# projesonberna.net
KiCad netlist of a schematic drawn in EAGLE
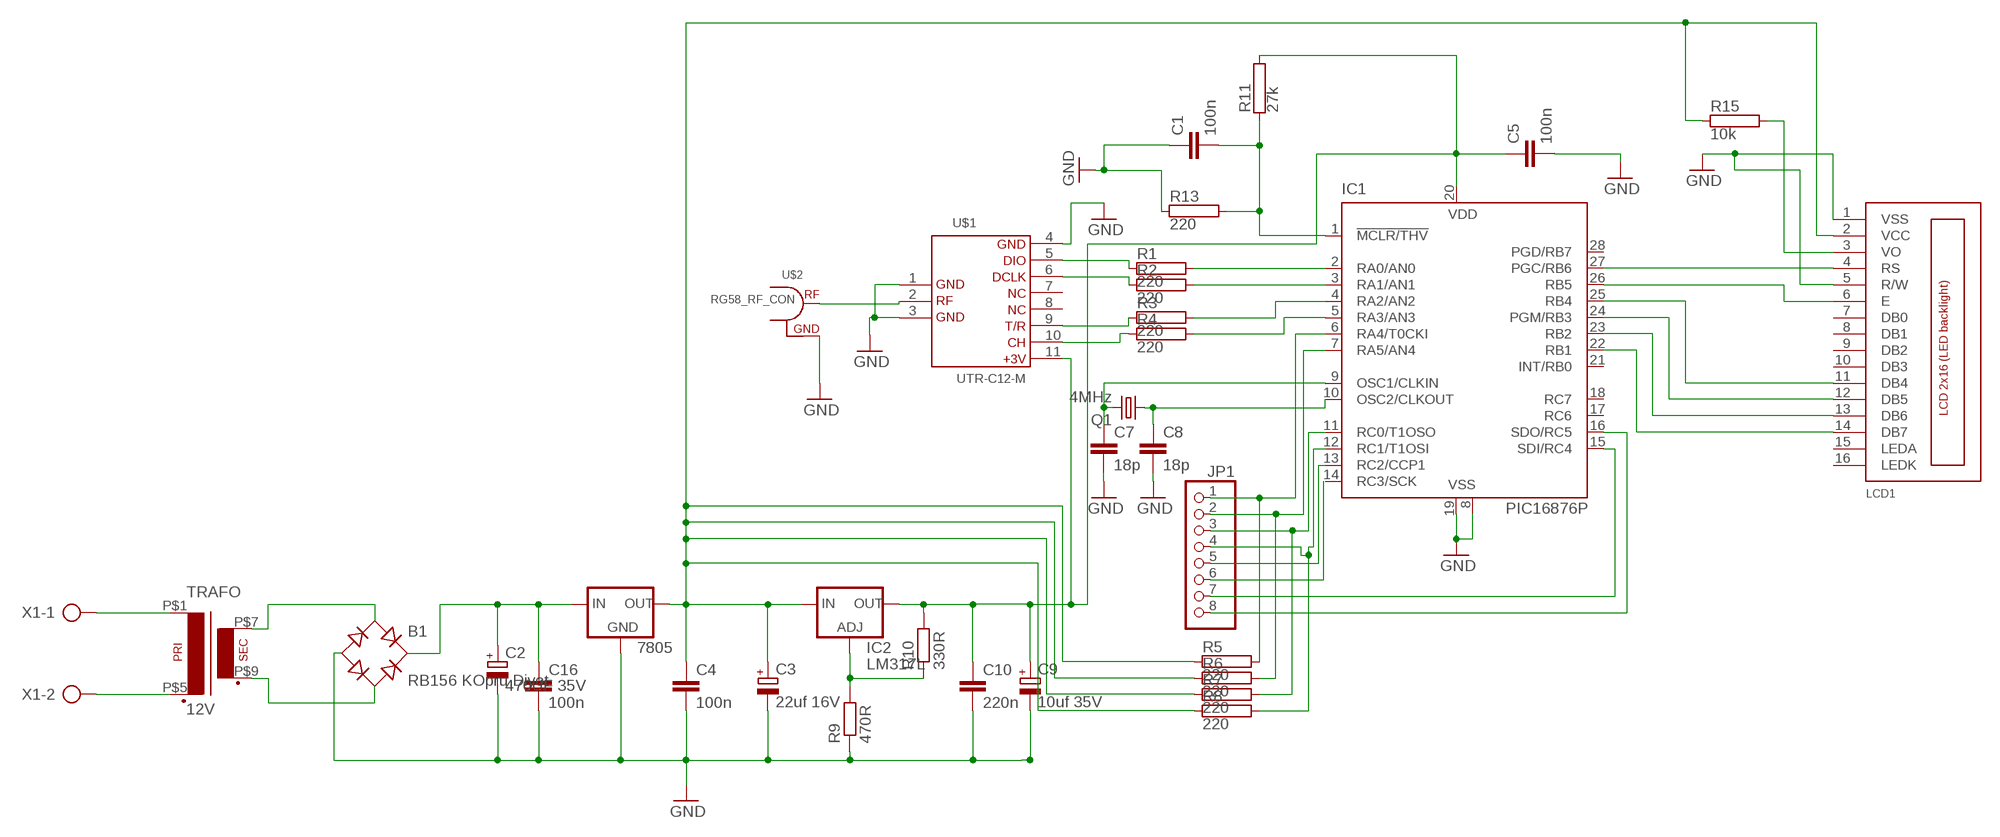
[diagram p0: schematic, sheet 1]

(export (version "E")
  (design (tool "Eeschema 10.0.6"))
  (components
    (comp (ref "7805")
      (value "78XXS")
      (footprint "eagle-import:78XXS")
      (libsource (lib "eagle-import") (part "78XXS"))
    )
    (comp (ref "B1")
      (value "RB156 KOpru Diyot")
      (footprint "eagle-import:RB1A")
      (libsource (lib "eagle-import") (part "RB1A"))
    )
    (comp (ref "C1")
      (value "100n")
      (footprint "eagle-import:C025-030X050")
      (libsource (lib "eagle-import") (part "C-EU025-030X050"))
    )
    (comp (ref "C2")
      (value "470UF 35V")
      (footprint "eagle-import:E3,5-10")
      (libsource (lib "eagle-import") (part "CPOL-EUE3.5-10"))
    )
    (comp (ref "C3")
      (value "22uf 16V")
      (footprint "eagle-import:E2,5-7")
      (libsource (lib "eagle-import") (part "CPOL-EUE2.5-7"))
    )
    (comp (ref "C4")
      (value "100n")
      (footprint "eagle-import:C050-025X075")
      (libsource (lib "eagle-import") (part "C-EU050-025X075"))
    )
    (comp (ref "C5")
      (value "100n")
      (footprint "eagle-import:C025-025X050")
      (libsource (lib "eagle-import") (part "C-EU025-025X050"))
    )
    (comp (ref "C7")
      (value "18p")
      (footprint "eagle-import:C025-025X050")
      (libsource (lib "eagle-import") (part "C-EU025-025X050"))
    )
    (comp (ref "C8")
      (value "18p")
      (footprint "eagle-import:C025-025X050")
      (libsource (lib "eagle-import") (part "C-EU025-025X050"))
    )
    (comp (ref "C9")
      (value "10uf 35V")
      (footprint "eagle-import:E2,5-7")
      (libsource (lib "eagle-import") (part "CPOL-EUE2.5-7"))
    )
    (comp (ref "C10")
      (value "220n")
      (footprint "eagle-import:C050-025X075")
      (libsource (lib "eagle-import") (part "C-EU050-025X075"))
    )
    (comp (ref "C16")
      (value "100n")
      (footprint "eagle-import:C050-025X075")
      (libsource (lib "eagle-import") (part "C-EU050-025X075"))
    )
    (comp (ref "IC1")
      (value "PIC16876P")
      (footprint "eagle-import:DIL28-3")
      (libsource (lib "eagle-import") (part "PIC16876P"))
    )
    (comp (ref "IC2")
      (value "LM317L")
      (footprint "eagle-import:317L")
      (libsource (lib "eagle-import") (part "LM317L"))
    )
    (comp (ref "JP1")
      (value "PINHD-1X8")
      (footprint "eagle-import:1X08")
      (libsource (lib "eagle-import") (part "PINHD-1X8"))
    )
    (comp (ref "LCD1")
      (value "LCD_2X16_SIL")
      (footprint "eagle-import:HY-1602F")
      (libsource (lib "eagle-import") (part "LCD_2X16_SIL"))
    )
    (comp (ref "Q1")
      (value "4MHz")
      (footprint "eagle-import:HC49_S")
      (libsource (lib "eagle-import") (part "CRYTALHC49S"))
    )
    (comp (ref "R1")
      (value "220")
      (footprint "eagle-import:AC04")
      (libsource (lib "eagle-import") (part "RAC04"))
    )
    (comp (ref "R2")
      (value "220")
      (footprint "eagle-import:AC04")
      (libsource (lib "eagle-import") (part "RAC04"))
    )
    (comp (ref "R3")
      (value "220")
      (footprint "eagle-import:AC04")
      (libsource (lib "eagle-import") (part "RAC04"))
    )
    (comp (ref "R4")
      (value "220")
      (footprint "eagle-import:AC04")
      (libsource (lib "eagle-import") (part "RAC04"))
    )
    (comp (ref "R5")
      (value "220")
      (footprint "eagle-import:AC04")
      (libsource (lib "eagle-import") (part "RAC04"))
    )
    (comp (ref "R6")
      (value "220")
      (footprint "eagle-import:AC04")
      (libsource (lib "eagle-import") (part "RAC04"))
    )
    (comp (ref "R7")
      (value "220")
      (footprint "eagle-import:AC04")
      (libsource (lib "eagle-import") (part "RAC04"))
    )
    (comp (ref "R8")
      (value "220")
      (footprint "eagle-import:AC04")
      (libsource (lib "eagle-import") (part "RAC04"))
    )
    (comp (ref "R9")
      (value "470R")
      (footprint "eagle-import:0207_10")
      (libsource (lib "eagle-import") (part "R-EU_0207/10"))
    )
    (comp (ref "R10")
      (value "330R")
      (footprint "eagle-import:0207_10")
      (libsource (lib "eagle-import") (part "R-EU_0207/10"))
    )
    (comp (ref "R11")
      (value "27k")
      (footprint "eagle-import:AC04")
      (libsource (lib "eagle-import") (part "RAC04"))
    )
    (comp (ref "R13")
      (value "220")
      (footprint "eagle-import:AC04")
      (libsource (lib "eagle-import") (part "RAC04"))
    )
    (comp (ref "R15")
      (value "10k")
      (footprint "eagle-import:AC04")
      (libsource (lib "eagle-import") (part "RAC04"))
    )
    (comp (ref "TRAFO")
      (value "12V")
      (footprint "eagle-import:E3031TRF")
      (libsource (lib "eagle-import") (part "TRAFO"))
    )
    (comp (ref "U$1")
      (value "UTR-C12-M")
      (footprint "eagle-import:UTR-C12-M")
      (libsource (lib "eagle-import") (part "UTR-C12-M"))
    )
    (comp (ref "U$2")
      (value "RG58_RF_CON")
      (footprint "eagle-import:RG58_RF_CON")
      (libsource (lib "eagle-import") (part "RG58_RF_CON"))
    )
    (comp (ref "X1")
      (value "AK300/3")
      (footprint "eagle-import:AK300_3")
      (libsource (lib "eagle-import") (part "AK300/3"))
    )
  )
  (nets
    (net (code "1") (name "GND") (class "Default")
      (node (ref "7805") (pin "GND") (pinfunction "GND_GND") (pintype "input"))
      (node (ref "B1") (pin "-") (pinfunction "-_-") (pintype "passive"))
      (node (ref "C1") (pin "1") (pinfunction "1_1") (pintype "passive"))
      (node (ref "C10") (pin "2") (pinfunction "2_2") (pintype "passive"))
      (node (ref "C16") (pin "2") (pinfunction "2_2") (pintype "passive"))
      (node (ref "C2") (pin "-") (pinfunction "-_-") (pintype "passive"))
      (node (ref "C3") (pin "-") (pinfunction "-_-") (pintype "passive"))
      (node (ref "C4") (pin "2") (pinfunction "2_2") (pintype "passive"))
      (node (ref "C5") (pin "2") (pinfunction "2_2") (pintype "passive"))
      (node (ref "C7") (pin "2") (pinfunction "2_2") (pintype "passive"))
      (node (ref "C8") (pin "2") (pinfunction "2_2") (pintype "passive"))
      (node (ref "C9") (pin "-") (pinfunction "-_-") (pintype "passive"))
      (node (ref "IC1") (pin "19") (pinfunction "VSS_19") (pintype "power_in"))
      (node (ref "IC1") (pin "8") (pinfunction "VSS_8") (pintype "power_in"))
      (node (ref "LCD1") (pin "1") (pinfunction "VSS_1") (pintype "power_in"))
      (node (ref "LCD1") (pin "5") (pinfunction "R/W_5") (pintype "input"))
      (node (ref "R13") (pin "1") (pinfunction "1_1") (pintype "passive"))
      (node (ref "R9") (pin "1") (pinfunction "1_1") (pintype "passive"))
      (node (ref "U$1") (pin "1") (pinfunction "1_1") (pintype "bidirectional"))
      (node (ref "U$1") (pin "3") (pinfunction "3_3") (pintype "bidirectional"))
      (node (ref "U$1") (pin "4") (pinfunction "4_4") (pintype "bidirectional"))
      (node (ref "U$2") (pin "GND") (pinfunction "GND_GND") (pintype "bidirectional"))
    )
    (net (code "2") (name "Net-(7805-PadIN)") (class "Default")
      (node (ref "7805") (pin "IN") (pinfunction "IN_IN") (pintype "input"))
      (node (ref "B1") (pin "+") (pinfunction "+_+") (pintype "passive"))
      (node (ref "C16") (pin "1") (pinfunction "1_1") (pintype "passive"))
      (node (ref "C2") (pin "+") (pinfunction "+_+") (pintype "passive"))
    )
    (net (code "3") (name "Net-(IC1-OSC1{slash}CLKIN)") (class "Default")
      (node (ref "C7") (pin "1") (pinfunction "1_1") (pintype "passive"))
      (node (ref "IC1") (pin "9") (pinfunction "OSC1/CLKIN_9") (pintype "input"))
      (node (ref "Q1") (pin "2") (pinfunction "2_2") (pintype "passive"))
    )
    (net (code "4") (name "Net-(IC1-OSC2{slash}CLKOUT)") (class "Default")
      (node (ref "C8") (pin "1") (pinfunction "1_1") (pintype "passive"))
      (node (ref "IC1") (pin "10") (pinfunction "OSC2/CLKOUT_10") (pintype "output"))
      (node (ref "Q1") (pin "1") (pinfunction "1_1") (pintype "passive"))
    )
    (net (code "5") (name "Net-(IC1-PGC{slash}RB6)") (class "Default")
      (node (ref "IC1") (pin "27") (pinfunction "PGC/RB6_27") (pintype "bidirectional"))
      (node (ref "LCD1") (pin "4") (pinfunction "RS_4") (pintype "input"))
    )
    (net (code "6") (name "Net-(IC1-PGM{slash}RB3)") (class "Default")
      (node (ref "IC1") (pin "24") (pinfunction "PGM/RB3_24") (pintype "bidirectional"))
      (node (ref "LCD1") (pin "12") (pinfunction "DB5_12") (pintype "bidirectional"))
    )
    (net (code "7") (name "Net-(IC1-RA0{slash}AN0)") (class "Default")
      (node (ref "IC1") (pin "2") (pinfunction "RA0/AN0_2") (pintype "bidirectional"))
      (node (ref "R1") (pin "2") (pinfunction "2_2") (pintype "passive"))
    )
    (net (code "8") (name "Net-(IC1-RA1{slash}AN1)") (class "Default")
      (node (ref "IC1") (pin "3") (pinfunction "RA1/AN1_3") (pintype "bidirectional"))
      (node (ref "R2") (pin "2") (pinfunction "2_2") (pintype "passive"))
    )
    (net (code "9") (name "Net-(IC1-RA2{slash}AN2)") (class "Default")
      (node (ref "IC1") (pin "4") (pinfunction "RA2/AN2_4") (pintype "bidirectional"))
      (node (ref "R3") (pin "2") (pinfunction "2_2") (pintype "passive"))
    )
    (net (code "10") (name "Net-(IC1-RA3{slash}AN3)") (class "Default")
      (node (ref "IC1") (pin "5") (pinfunction "RA3/AN3_5") (pintype "bidirectional"))
      (node (ref "R4") (pin "2") (pinfunction "2_2") (pintype "passive"))
    )
    (net (code "11") (name "Net-(IC1-RA4{slash}T0CKI)") (class "Default")
      (node (ref "IC1") (pin "6") (pinfunction "RA4/T0CKI_6") (pintype "bidirectional"))
      (node (ref "JP1") (pin "1") (pinfunction "1_1") (pintype "passive"))
      (node (ref "R5") (pin "2") (pinfunction "2_2") (pintype "passive"))
    )
    (net (code "12") (name "Net-(IC1-RA5{slash}AN4)") (class "Default")
      (node (ref "IC1") (pin "7") (pinfunction "RA5/AN4_7") (pintype "bidirectional"))
      (node (ref "JP1") (pin "2") (pinfunction "2_2") (pintype "passive"))
      (node (ref "R6") (pin "2") (pinfunction "2_2") (pintype "passive"))
    )
    (net (code "13") (name "Net-(IC1-RB1)") (class "Default")
      (node (ref "IC1") (pin "22") (pinfunction "RB1_22") (pintype "bidirectional"))
      (node (ref "LCD1") (pin "14") (pinfunction "DB7_14") (pintype "bidirectional"))
    )
    (net (code "14") (name "Net-(IC1-RB2)") (class "Default")
      (node (ref "IC1") (pin "23") (pinfunction "RB2_23") (pintype "bidirectional"))
      (node (ref "LCD1") (pin "13") (pinfunction "DB6_13") (pintype "bidirectional"))
    )
    (net (code "15") (name "Net-(IC1-RB4)") (class "Default")
      (node (ref "IC1") (pin "25") (pinfunction "RB4_25") (pintype "bidirectional"))
      (node (ref "LCD1") (pin "11") (pinfunction "DB4_11") (pintype "bidirectional"))
    )
    (net (code "16") (name "Net-(IC1-RB5)") (class "Default")
      (node (ref "IC1") (pin "26") (pinfunction "RB5_26") (pintype "bidirectional"))
      (node (ref "LCD1") (pin "6") (pinfunction "E_6") (pintype "input"))
    )
    (net (code "17") (name "Net-(IC1-RC0{slash}T1OSO)") (class "Default")
      (node (ref "IC1") (pin "11") (pinfunction "RC0/T1OSO_11") (pintype "bidirectional"))
      (node (ref "JP1") (pin "3") (pinfunction "3_3") (pintype "passive"))
      (node (ref "R7") (pin "2") (pinfunction "2_2") (pintype "passive"))
    )
    (net (code "18") (name "Net-(IC1-RC1{slash}T1OSI)") (class "Default")
      (node (ref "IC1") (pin "12") (pinfunction "RC1/T1OSI_12") (pintype "bidirectional"))
      (node (ref "JP1") (pin "4") (pinfunction "4_4") (pintype "passive"))
      (node (ref "R8") (pin "2") (pinfunction "2_2") (pintype "passive"))
    )
    (net (code "19") (name "Net-(IC1-RC2{slash}CCP1)") (class "Default")
      (node (ref "IC1") (pin "13") (pinfunction "RC2/CCP1_13") (pintype "bidirectional"))
      (node (ref "JP1") (pin "5") (pinfunction "5_5") (pintype "passive"))
    )
    (net (code "20") (name "Net-(IC1-SDI{slash}RC4)") (class "Default")
      (node (ref "IC1") (pin "15") (pinfunction "SDI/RC4_15") (pintype "bidirectional"))
      (node (ref "JP1") (pin "7") (pinfunction "7_7") (pintype "passive"))
    )
    (net (code "21") (name "Net-(IC1-SDO{slash}RC5)") (class "Default")
      (node (ref "IC1") (pin "16") (pinfunction "SDO/RC5_16") (pintype "bidirectional"))
      (node (ref "JP1") (pin "8") (pinfunction "8_8") (pintype "passive"))
    )
    (net (code "22") (name "Net-(IC1-VDD)") (class "Default")
      (node (ref "C10") (pin "1") (pinfunction "1_1") (pintype "passive"))
      (node (ref "C5") (pin "1") (pinfunction "1_1") (pintype "passive"))
      (node (ref "C9") (pin "+") (pinfunction "+_+") (pintype "passive"))
      (node (ref "IC1") (pin "20") (pinfunction "VDD_20") (pintype "power_in"))
      (node (ref "IC2") (pin "2") (pinfunction "OUT_2") (pintype "passive"))
      (node (ref "R10") (pin "2") (pinfunction "2_2") (pintype "passive"))
      (node (ref "R11") (pin "2") (pinfunction "2_2") (pintype "passive"))
      (node (ref "U$1") (pin "11") (pinfunction "11_11") (pintype "bidirectional"))
    )
    (net (code "23") (name "Net-(IC1-~{MCLR{slash}THV})") (class "Default")
      (node (ref "C1") (pin "2") (pinfunction "2_2") (pintype "passive"))
      (node (ref "IC1") (pin "1") (pinfunction "~{MCLR/THV}_1") (pintype "input"))
      (node (ref "R11") (pin "1") (pinfunction "1_1") (pintype "passive"))
      (node (ref "R13") (pin "2") (pinfunction "2_2") (pintype "passive"))
    )
    (net (code "24") (name "Net-(IC2-ADJ)") (class "Default")
      (node (ref "IC2") (pin "1") (pinfunction "ADJ_1") (pintype "input"))
      (node (ref "R10") (pin "1") (pinfunction "1_1") (pintype "passive"))
      (node (ref "R9") (pin "2") (pinfunction "2_2") (pintype "passive"))
    )
    (net (code "25") (name "Net-(IC2-IN)") (class "Default")
      (node (ref "7805") (pin "OUT") (pinfunction "OUT_OUT") (pintype "passive"))
      (node (ref "C3") (pin "+") (pinfunction "+_+") (pintype "passive"))
      (node (ref "C4") (pin "1") (pinfunction "1_1") (pintype "passive"))
      (node (ref "IC2") (pin "3") (pinfunction "IN_3") (pintype "input"))
      (node (ref "LCD1") (pin "2") (pinfunction "VCC_2") (pintype "power_in"))
      (node (ref "R15") (pin "1") (pinfunction "1_1") (pintype "passive"))
      (node (ref "R5") (pin "1") (pinfunction "1_1") (pintype "passive"))
      (node (ref "R6") (pin "1") (pinfunction "1_1") (pintype "passive"))
      (node (ref "R7") (pin "1") (pinfunction "1_1") (pintype "passive"))
      (node (ref "R8") (pin "1") (pinfunction "1_1") (pintype "passive"))
    )
    (net (code "26") (name "Net-(LCD1-VO)") (class "Default")
      (node (ref "LCD1") (pin "3") (pinfunction "VO_3") (pintype "input"))
      (node (ref "R15") (pin "2") (pinfunction "2_2") (pintype "passive"))
    )
    (net (code "27") (name "Net-(R1-Pad1)") (class "Default")
      (node (ref "R1") (pin "1") (pinfunction "1_1") (pintype "passive"))
      (node (ref "U$1") (pin "5") (pinfunction "5_5") (pintype "bidirectional"))
    )
    (net (code "28") (name "Net-(R2-Pad1)") (class "Default")
      (node (ref "R2") (pin "1") (pinfunction "1_1") (pintype "passive"))
      (node (ref "U$1") (pin "6") (pinfunction "6_6") (pintype "bidirectional"))
    )
    (net (code "29") (name "Net-(R3-Pad1)") (class "Default")
      (node (ref "R3") (pin "1") (pinfunction "1_1") (pintype "passive"))
      (node (ref "U$1") (pin "9") (pinfunction "9_9") (pintype "bidirectional"))
    )
    (net (code "30") (name "Net-(R4-Pad1)") (class "Default")
      (node (ref "R4") (pin "1") (pinfunction "1_1") (pintype "passive"))
      (node (ref "U$1") (pin "10") (pinfunction "10_10") (pintype "bidirectional"))
    )
    (net (code "31") (name "Net-(TRAFO-1)") (class "Default")
      (node (ref "TRAFO") (pin "P$1") (pinfunction "1_P$1") (pintype "passive"))
      (node (ref "X1") (pin "1") (pinfunction "KL_1") (pintype "passive"))
    )
    (net (code "32") (name "Net-(TRAFO-5)") (class "Default")
      (node (ref "TRAFO") (pin "P$5") (pinfunction "5_P$5") (pintype "passive"))
      (node (ref "X1") (pin "2") (pinfunction "KL_2") (pintype "passive"))
    )
    (net (code "33") (name "Net-(TRAFO-7)") (class "Default")
      (node (ref "B1") (pin "AC1") (pinfunction "AC1_AC1") (pintype "passive"))
      (node (ref "TRAFO") (pin "P$7") (pinfunction "7_P$7") (pintype "passive"))
    )
    (net (code "34") (name "Net-(TRAFO-9)") (class "Default")
      (node (ref "B1") (pin "AC2") (pinfunction "AC2_AC2") (pintype "passive"))
      (node (ref "TRAFO") (pin "P$9") (pinfunction "9_P$9") (pintype "passive"))
    )
    (net (code "35") (name "Net-(U$1-Pad2)") (class "Default")
      (node (ref "U$1") (pin "2") (pinfunction "2_2") (pintype "bidirectional"))
      (node (ref "U$2") (pin "RF") (pinfunction "RF_RF") (pintype "bidirectional"))
    )
    (net (code "36") (name "unconnected-(IC1-INT{slash}RB0-Pad21)") (class "Default")
      (node (ref "IC1") (pin "21") (pinfunction "INT/RB0_21") (pintype "bidirectional"))
    )
    (net (code "37") (name "unconnected-(IC1-PGD{slash}RB7-Pad28)") (class "Default")
      (node (ref "IC1") (pin "28") (pinfunction "PGD/RB7_28") (pintype "bidirectional"))
    )
    (net (code "38") (name "unconnected-(IC1-RC3{slash}SCK-Pad14)") (class "Default")
      (node (ref "IC1") (pin "14") (pinfunction "RC3/SCK_14") (pintype "bidirectional"))
    )
    (net (code "39") (name "unconnected-(IC1-RC6-Pad17)") (class "Default")
      (node (ref "IC1") (pin "17") (pinfunction "RC6_17") (pintype "bidirectional"))
    )
    (net (code "40") (name "unconnected-(IC1-RC7-Pad18)") (class "Default")
      (node (ref "IC1") (pin "18") (pinfunction "RC7_18") (pintype "bidirectional"))
    )
    (net (code "41") (name "unconnected-(JP1-Pad6)") (class "Default")
      (node (ref "JP1") (pin "6") (pinfunction "6_6") (pintype "passive"))
    )
    (net (code "42") (name "unconnected-(LCD1-DB0-Pad7)") (class "Default")
      (node (ref "LCD1") (pin "7") (pinfunction "DB0_7") (pintype "bidirectional"))
    )
    (net (code "43") (name "unconnected-(LCD1-DB1-Pad8)") (class "Default")
      (node (ref "LCD1") (pin "8") (pinfunction "DB1_8") (pintype "bidirectional"))
    )
    (net (code "44") (name "unconnected-(LCD1-DB2-Pad9)") (class "Default")
      (node (ref "LCD1") (pin "9") (pinfunction "DB2_9") (pintype "bidirectional"))
    )
    (net (code "45") (name "unconnected-(LCD1-DB3-Pad10)") (class "Default")
      (node (ref "LCD1") (pin "10") (pinfunction "DB3_10") (pintype "bidirectional"))
    )
    (net (code "46") (name "unconnected-(LCD1-LEDA-Pad15)") (class "Default")
      (node (ref "LCD1") (pin "15") (pinfunction "LEDA_15") (pintype "passive"))
    )
    (net (code "47") (name "unconnected-(LCD1-LEDK-Pad16)") (class "Default")
      (node (ref "LCD1") (pin "16") (pinfunction "LEDK_16") (pintype "passive"))
    )
    (net (code "48") (name "unconnected-(U$1-Pad7)") (class "Default")
      (node (ref "U$1") (pin "7") (pinfunction "7_7") (pintype "bidirectional"))
    )
    (net (code "49") (name "unconnected-(U$1-Pad8)") (class "Default")
      (node (ref "U$1") (pin "8") (pinfunction "8_8") (pintype "bidirectional"))
    )
  )
)
